# USB_Modificado.net
KiCad netlist of a schematic drawn in Altium Designer
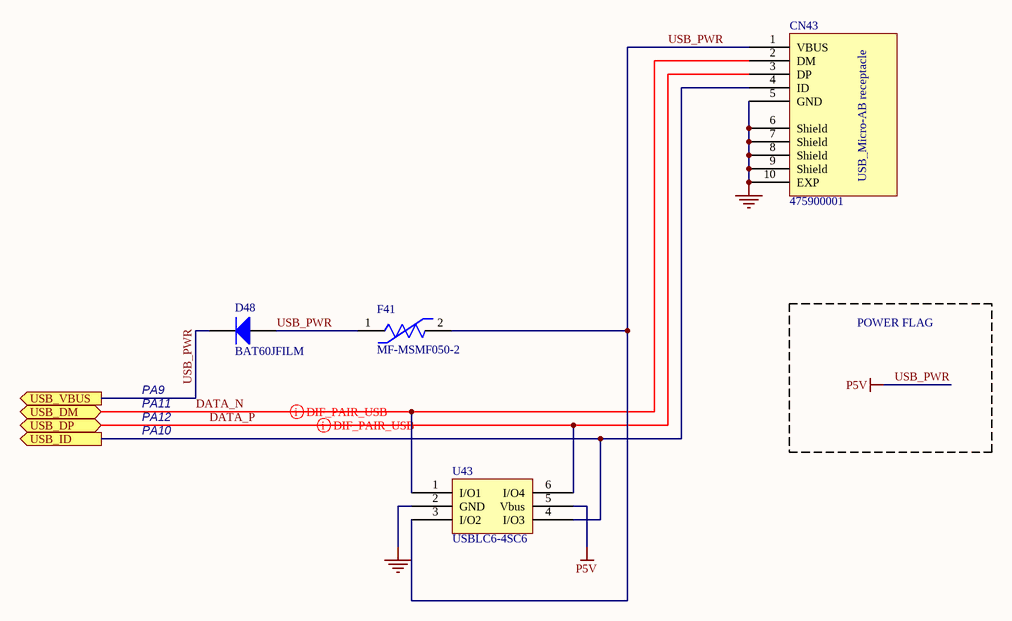
[diagram p0: USB_Modificado.SchDoc]

(export (version "E")
  (design (tool "Eeschema 10.0.6"))
  (components
    (comp (ref "CN43")
      (value "475900001")
      (footprint "MOLEX_47590001")
      (libsource (lib "mb1045") (part "475900001"))
    )
    (comp (ref "D48")
      (value "BAT60JFILM")
      (footprint "SOD-323")
      (libsource (lib "MB1137") (part "BAT60JFILM"))
    )
    (comp (ref "F41")
      (value "MF-MSMF050-2")
      (footprint "FP-MF-MSMF050-2-MFG")
      (description "PTC RESET FUSE 15V 500MA 1812")
      (fields
        (field (name "MANUFACTURER") "Bourns")
        (field (name "OCTOPART") "https://octopart.com/mf-msmf050-2-bourns-28047")
      )
      (libsource (lib "Altium Content Vault") (part "fc31388045fc42ab786d6d00b506e9f"))
    )
    (comp (ref "U43")
      (value "USBLC6-4SC6")
      (footprint "SOT23-6L")
      (libsource (lib "MB1137") (part "USBLC6-4SC6"))
    )
  )
  (nets
    (net (code "1") (name "/DATA_N") (class "Default")
      (node (ref "CN43") (pin "2") (pinfunction "DM_2") (pintype "passive"))
      (node (ref "U43") (pin "1") (pinfunction "I/O1_1") (pintype "passive"))
    )
    (net (code "2") (name "/DATA_P") (class "Default")
      (node (ref "CN43") (pin "3") (pinfunction "DP_3") (pintype "passive"))
      (node (ref "U43") (pin "6") (pinfunction "I/O4_6") (pintype "passive"))
    )
    (net (code "3") (name "/USB_ID") (class "Default")
      (node (ref "CN43") (pin "4") (pinfunction "ID_4") (pintype "passive"))
      (node (ref "U43") (pin "4") (pinfunction "I/O3_4") (pintype "passive"))
    )
    (net (code "4") (name "GND") (class "Default")
      (node (ref "CN43") (pin "10") (pinfunction "EXP_10") (pintype "passive"))
      (node (ref "CN43") (pin "5") (pinfunction "GND_5") (pintype "passive"))
      (node (ref "CN43") (pin "6") (pinfunction "Shield_6") (pintype "passive"))
      (node (ref "CN43") (pin "7") (pinfunction "Shield_7") (pintype "passive"))
      (node (ref "CN43") (pin "8") (pinfunction "Shield_8") (pintype "passive"))
      (node (ref "CN43") (pin "9") (pinfunction "Shield_9") (pintype "passive"))
      (node (ref "U43") (pin "2") (pinfunction "GND_2") (pintype "passive"))
    )
    (net (code "5") (name "P5V") (class "Default")
      (node (ref "CN43") (pin "1") (pinfunction "VBUS_1") (pintype "passive"))
      (node (ref "D48") (pin "1") (pinfunction "A_1") (pintype "passive"))
      (node (ref "D48") (pin "2") (pinfunction "K_2") (pintype "passive"))
      (node (ref "F41") (pin "1") (pinfunction "1_1") (pintype "passive"))
      (node (ref "F41") (pin "2") (pinfunction "2_2") (pintype "passive"))
      (node (ref "U43") (pin "3") (pinfunction "I/O2_3") (pintype "passive"))
      (node (ref "U43") (pin "5") (pinfunction "Vbus_5") (pintype "passive"))
    )
  )
)
